# eSIM.net
KiCad netlist of a schematic drawn in Altium Designer
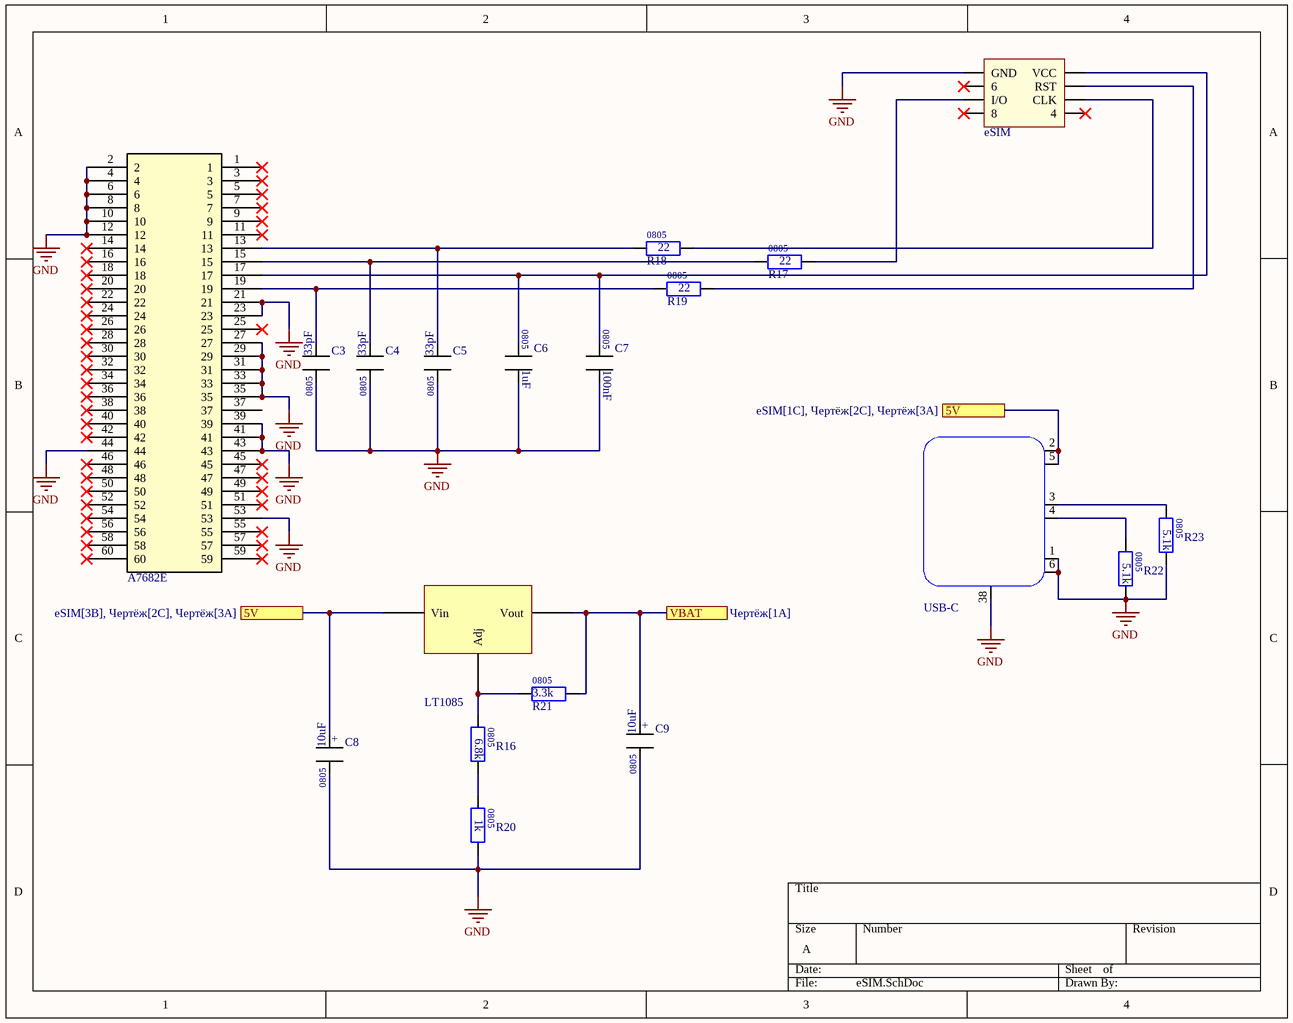
[diagram p0: eSIM.SchDoc]

(export (version "E")
  (design (tool "Eeschema 10.0.6"))
  (components
    (comp (ref "A7682E_J204") (value "A7682E") (footprint "A7682") (libsource (lib "Plat") (part "A7682E")))
    (comp (ref "C3")
      (value "CC080533pF")
      (footprint "СС0805")
      (description "CC0805_33pF")
      (libsource (lib "Component") (part "CC080533pF"))
    )
    (comp (ref "C4")
      (value "CC080533pF")
      (footprint "СС0805")
      (description "CC0805_33pF")
      (libsource (lib "Component") (part "CC080533pF"))
    )
    (comp (ref "C5")
      (value "CC080533pF")
      (footprint "СС0805")
      (description "CC0805_33pF")
      (libsource (lib "Component") (part "CC080533pF"))
    )
    (comp (ref "C6")
      (value "capacitor")
      (footprint "СС0805")
      (description "CC0805_1uF")
      (libsource (lib "Component") (part "CC08051uF"))
    )
    (comp (ref "C7")
      (value "capacitor")
      (footprint "СС0805")
      (description "CC0805_100nF")
      (libsource (lib "Component") (part "CC0805100nF"))
    )
    (comp (ref "C8")
      (value "capacitor")
      (footprint "CAP JAMOCON")
      (description "CE0805_10uF")
      (libsource (lib "Component") (part "CE080510uF"))
    )
    (comp (ref "C9")
      (value "capacitor")
      (footprint "CAP JAMOCON")
      (description "CE0805_10uF")
      (libsource (lib "Component") (part "CE080510uF"))
    )
    (comp (ref "eSIM1") (value "eSIM") (footprint "eSIM") (libsource (lib "Plat") (part "eSIM")))
    (comp (ref "LT1") (value "LT1085") (footprint "LD1058-1") (libsource (lib "Plat") (part "LT1085")))
    (comp (ref "R16")
      (value "Resistor")
      (footprint "R0805")
      (description "CR0805_6.8kR")
      (libsource (lib "Component") (part "CR08056.8kR"))
    )
    (comp (ref "R17")
      (value "Resistor")
      (footprint "R0805")
      (description "CR0805_22R")
      (libsource (lib "Component") (part "CR080522R"))
    )
    (comp (ref "R18")
      (value "Resistor")
      (footprint "R0805")
      (description "CR0805_22R")
      (libsource (lib "Component") (part "CR080522R"))
    )
    (comp (ref "R19")
      (value "Resistor")
      (footprint "R0805")
      (description "CR0805_22R")
      (libsource (lib "Component") (part "CR080522R"))
    )
    (comp (ref "R20")
      (value "Resistor")
      (footprint "R0805")
      (description "CR0805_1kR")
      (libsource (lib "Component") (part "CR08051kR"))
    )
    (comp (ref "R21")
      (value "Resistor")
      (footprint "R0805")
      (description "CR0805_3.3kR")
      (libsource (lib "Component") (part "CR08053.3kR"))
    )
    (comp (ref "R22")
      (value "Resistor")
      (footprint "R0805")
      (description "CR08055.1kR")
      (libsource (lib "Component") (part "CR08055.1kR"))
    )
    (comp (ref "R23")
      (value "Resistor")
      (footprint "R0805")
      (description "CR08055.1kR")
      (libsource (lib "Component") (part "CR08055.1kR"))
    )
    (comp (ref "USB-C1") (value "USB-C") (footprint "USB C") (libsource (lib "Plat") (part "USB-C")))
  )
  (nets
    (net (code "1") (name "/5V") (class "Default")
      (node (ref "C8") (pin "2") (pinfunction "2_2") (pintype "passive"))
      (node (ref "LT1") (pin "Vin") (pinfunction "Vin_Vin") (pintype "passive"))
      (node (ref "USB-C1") (pin "2") (pinfunction "VBAS_2") (pintype "passive"))
      (node (ref "USB-C1") (pin "5") (pinfunction "VBAS_5") (pintype "passive"))
    )
    (net (code "2") (name "/VBAT") (class "Default")
      (node (ref "C9") (pin "2") (pinfunction "2_2") (pintype "passive"))
      (node (ref "LT1") (pin "Vout") (pinfunction "Vout_Vout") (pintype "passive"))
      (node (ref "R21") (pin "1") (pinfunction "1_1") (pintype "passive"))
    )
    (net (code "3") (name "GND") (class "Default")
      (node (ref "A7682E_J204") (pin "10") (pinfunction "10_10") (pintype "passive"))
      (node (ref "A7682E_J204") (pin "12") (pinfunction "12_12") (pintype "passive"))
      (node (ref "A7682E_J204") (pin "2") (pinfunction "2_2") (pintype "passive"))
      (node (ref "A7682E_J204") (pin "21") (pinfunction "21_21") (pintype "passive"))
      (node (ref "A7682E_J204") (pin "23") (pinfunction "23_23") (pintype "passive"))
      (node (ref "A7682E_J204") (pin "27") (pinfunction "27_27") (pintype "passive"))
      (node (ref "A7682E_J204") (pin "29") (pinfunction "29_29") (pintype "passive"))
      (node (ref "A7682E_J204") (pin "31") (pinfunction "31_31") (pintype "passive"))
      (node (ref "A7682E_J204") (pin "33") (pinfunction "33_33") (pintype "passive"))
      (node (ref "A7682E_J204") (pin "35") (pinfunction "35_35") (pintype "passive"))
      (node (ref "A7682E_J204") (pin "39") (pinfunction "39_39") (pintype "passive"))
      (node (ref "A7682E_J204") (pin "4") (pinfunction "4_4") (pintype "passive"))
      (node (ref "A7682E_J204") (pin "41") (pinfunction "41_41") (pintype "passive"))
      (node (ref "A7682E_J204") (pin "43") (pinfunction "43_43") (pintype "passive"))
      (node (ref "A7682E_J204") (pin "44") (pinfunction "44_44") (pintype "passive"))
      (node (ref "A7682E_J204") (pin "53") (pinfunction "53_53") (pintype "passive"))
      (node (ref "A7682E_J204") (pin "6") (pinfunction "6_6") (pintype "passive"))
      (node (ref "A7682E_J204") (pin "8") (pinfunction "8_8") (pintype "passive"))
      (node (ref "C3") (pin "2") (pinfunction "2_2") (pintype "passive"))
      (node (ref "C4") (pin "2") (pinfunction "2_2") (pintype "passive"))
      (node (ref "C5") (pin "2") (pinfunction "2_2") (pintype "passive"))
      (node (ref "C6") (pin "2") (pinfunction "2_2") (pintype "passive"))
      (node (ref "C7") (pin "3") (pinfunction "3_3") (pintype "passive"))
      (node (ref "C8") (pin "3") (pinfunction "3_3") (pintype "passive"))
      (node (ref "C9") (pin "3") (pinfunction "3_3") (pintype "passive"))
      (node (ref "R20") (pin "1") (pinfunction "1_1") (pintype "passive"))
      (node (ref "R22") (pin "1") (pinfunction "1_1") (pintype "passive"))
      (node (ref "R23") (pin "1") (pinfunction "1_1") (pintype "passive"))
      (node (ref "USB-C1") (pin "1") (pinfunction "GND_1") (pintype "passive"))
      (node (ref "USB-C1") (pin "38") (pinfunction "SHIELD_38") (pintype "passive"))
      (node (ref "USB-C1") (pin "6") (pinfunction "GND_6") (pintype "passive"))
      (node (ref "eSIM1") (pin "5") (pinfunction "GND_5") (pintype "passive"))
    )
    (net (code "4") (name "Net-(A7682E_J204-Pad13)") (class "Default")
      (node (ref "A7682E_J204") (pin "13") (pinfunction "13_13") (pintype "passive"))
      (node (ref "C5") (pin "3") (pinfunction "3_3") (pintype "passive"))
      (node (ref "R18") (pin "0") (pinfunction "0_0") (pintype "passive"))
    )
    (net (code "5") (name "Net-(A7682E_J204-Pad15)") (class "Default")
      (node (ref "A7682E_J204") (pin "15") (pinfunction "15_15") (pintype "passive"))
      (node (ref "C4") (pin "3") (pinfunction "3_3") (pintype "passive"))
      (node (ref "R17") (pin "0") (pinfunction "0_0") (pintype "passive"))
    )
    (net (code "6") (name "Net-(A7682E_J204-Pad19)") (class "Default")
      (node (ref "A7682E_J204") (pin "19") (pinfunction "19_19") (pintype "passive"))
      (node (ref "C3") (pin "3") (pinfunction "3_3") (pintype "passive"))
      (node (ref "R19") (pin "0") (pinfunction "0_0") (pintype "passive"))
    )
    (net (code "7") (name "Net-(LT1-PadAdj)") (class "Default")
      (node (ref "LT1") (pin "Adj") (pinfunction "Adj_Adj") (pintype "passive"))
      (node (ref "R16") (pin "0") (pinfunction "0_0") (pintype "passive"))
      (node (ref "R21") (pin "0") (pinfunction "0_0") (pintype "passive"))
    )
    (net (code "8") (name "Net-(R16-Pad1)") (class "Default")
      (node (ref "R16") (pin "1") (pinfunction "1_1") (pintype "passive"))
      (node (ref "R20") (pin "0") (pinfunction "0_0") (pintype "passive"))
    )
    (net (code "9") (name "Net-(USB-C1-CC1)") (class "Default")
      (node (ref "R23") (pin "0") (pinfunction "0_0") (pintype "passive"))
      (node (ref "USB-C1") (pin "3") (pinfunction "CC1_3") (pintype "passive"))
    )
    (net (code "10") (name "Net-(USB-C1-CC2)") (class "Default")
      (node (ref "R22") (pin "0") (pinfunction "0_0") (pintype "passive"))
      (node (ref "USB-C1") (pin "4") (pinfunction "CC2_4") (pintype "passive"))
    )
    (net (code "11") (name "Net-(eSIM1-CLK)") (class "Default")
      (node (ref "R18") (pin "1") (pinfunction "1_1") (pintype "passive"))
      (node (ref "eSIM1") (pin "3") (pinfunction "CLK_3") (pintype "passive"))
    )
    (net (code "12") (name "Net-(eSIM1-I{slash}O)") (class "Default")
      (node (ref "R17") (pin "1") (pinfunction "1_1") (pintype "passive"))
      (node (ref "eSIM1") (pin "7") (pinfunction "I/O_7") (pintype "passive"))
    )
    (net (code "13") (name "Net-(eSIM1-RST)") (class "Default")
      (node (ref "R19") (pin "1") (pinfunction "1_1") (pintype "passive"))
      (node (ref "eSIM1") (pin "2") (pinfunction "RST_2") (pintype "passive"))
    )
    (net (code "14") (name "Net-(eSIM1-VCC)") (class "Default")
      (node (ref "A7682E_J204") (pin "17") (pinfunction "17_17") (pintype "passive"))
      (node (ref "C6") (pin "3") (pinfunction "3_3") (pintype "passive"))
      (node (ref "C7") (pin "2") (pinfunction "2_2") (pintype "passive"))
      (node (ref "eSIM1") (pin "1") (pinfunction "VCC_1") (pintype "passive"))
    )
    (net (code "15") (name "unconnected-(A7682E_J204-Pad1)") (class "Default")
      (node (ref "A7682E_J204") (pin "1") (pinfunction "1_1") (pintype "passive+no_connect"))
    )
    (net (code "16") (name "unconnected-(A7682E_J204-Pad3)") (class "Default")
      (node (ref "A7682E_J204") (pin "3") (pinfunction "3_3") (pintype "passive+no_connect"))
    )
    (net (code "17") (name "unconnected-(A7682E_J204-Pad5)") (class "Default")
      (node (ref "A7682E_J204") (pin "5") (pinfunction "5_5") (pintype "passive+no_connect"))
    )
    (net (code "18") (name "unconnected-(A7682E_J204-Pad7)") (class "Default")
      (node (ref "A7682E_J204") (pin "7") (pinfunction "7_7") (pintype "passive+no_connect"))
    )
    (net (code "19") (name "unconnected-(A7682E_J204-Pad9)") (class "Default")
      (node (ref "A7682E_J204") (pin "9") (pinfunction "9_9") (pintype "passive+no_connect"))
    )
    (net (code "20") (name "unconnected-(A7682E_J204-Pad11)") (class "Default")
      (node (ref "A7682E_J204") (pin "11") (pinfunction "11_11") (pintype "passive+no_connect"))
    )
    (net (code "21") (name "unconnected-(A7682E_J204-Pad14)") (class "Default")
      (node (ref "A7682E_J204") (pin "14") (pinfunction "14_14") (pintype "passive+no_connect"))
    )
    (net (code "22") (name "unconnected-(A7682E_J204-Pad16)") (class "Default")
      (node (ref "A7682E_J204") (pin "16") (pinfunction "16_16") (pintype "passive+no_connect"))
    )
    (net (code "23") (name "unconnected-(A7682E_J204-Pad18)") (class "Default")
      (node (ref "A7682E_J204") (pin "18") (pinfunction "18_18") (pintype "passive+no_connect"))
    )
    (net (code "24") (name "unconnected-(A7682E_J204-Pad20)") (class "Default")
      (node (ref "A7682E_J204") (pin "20") (pinfunction "20_20") (pintype "passive+no_connect"))
    )
    (net (code "25") (name "unconnected-(A7682E_J204-Pad22)") (class "Default")
      (node (ref "A7682E_J204") (pin "22") (pinfunction "22_22") (pintype "passive+no_connect"))
    )
    (net (code "26") (name "unconnected-(A7682E_J204-Pad24)") (class "Default")
      (node (ref "A7682E_J204") (pin "24") (pinfunction "24_24") (pintype "passive+no_connect"))
    )
    (net (code "27") (name "unconnected-(A7682E_J204-Pad25)") (class "Default")
      (node (ref "A7682E_J204") (pin "25") (pinfunction "25_25") (pintype "passive+no_connect"))
    )
    (net (code "28") (name "unconnected-(A7682E_J204-Pad26)") (class "Default")
      (node (ref "A7682E_J204") (pin "26") (pinfunction "26_26") (pintype "passive+no_connect"))
    )
    (net (code "29") (name "unconnected-(A7682E_J204-Pad28)") (class "Default")
      (node (ref "A7682E_J204") (pin "28") (pinfunction "28_28") (pintype "passive+no_connect"))
    )
    (net (code "30") (name "unconnected-(A7682E_J204-Pad30)") (class "Default")
      (node (ref "A7682E_J204") (pin "30") (pinfunction "30_30") (pintype "passive+no_connect"))
    )
    (net (code "31") (name "unconnected-(A7682E_J204-Pad32)") (class "Default")
      (node (ref "A7682E_J204") (pin "32") (pinfunction "32_32") (pintype "passive+no_connect"))
    )
    (net (code "32") (name "unconnected-(A7682E_J204-Pad34)") (class "Default")
      (node (ref "A7682E_J204") (pin "34") (pinfunction "34_34") (pintype "passive+no_connect"))
    )
    (net (code "33") (name "unconnected-(A7682E_J204-Pad36)") (class "Default")
      (node (ref "A7682E_J204") (pin "36") (pinfunction "36_36") (pintype "passive+no_connect"))
    )
    (net (code "34") (name "unconnected-(A7682E_J204-Pad37)") (class "Default")
      (node (ref "A7682E_J204") (pin "37") (pinfunction "37_37") (pintype "passive"))
    )
    (net (code "35") (name "unconnected-(A7682E_J204-Pad38)") (class "Default")
      (node (ref "A7682E_J204") (pin "38") (pinfunction "38_38") (pintype "passive+no_connect"))
    )
    (net (code "36") (name "unconnected-(A7682E_J204-Pad40)") (class "Default")
      (node (ref "A7682E_J204") (pin "40") (pinfunction "40_40") (pintype "passive+no_connect"))
    )
    (net (code "37") (name "unconnected-(A7682E_J204-Pad42)") (class "Default")
      (node (ref "A7682E_J204") (pin "42") (pinfunction "42_42") (pintype "passive+no_connect"))
    )
    (net (code "38") (name "unconnected-(A7682E_J204-Pad45)") (class "Default")
      (node (ref "A7682E_J204") (pin "45") (pinfunction "45_45") (pintype "passive+no_connect"))
    )
    (net (code "39") (name "unconnected-(A7682E_J204-Pad46)") (class "Default")
      (node (ref "A7682E_J204") (pin "46") (pinfunction "46_46") (pintype "passive+no_connect"))
    )
    (net (code "40") (name "unconnected-(A7682E_J204-Pad47)") (class "Default")
      (node (ref "A7682E_J204") (pin "47") (pinfunction "47_47") (pintype "passive+no_connect"))
    )
    (net (code "41") (name "unconnected-(A7682E_J204-Pad48)") (class "Default")
      (node (ref "A7682E_J204") (pin "48") (pinfunction "48_48") (pintype "passive+no_connect"))
    )
    (net (code "42") (name "unconnected-(A7682E_J204-Pad49)") (class "Default")
      (node (ref "A7682E_J204") (pin "49") (pinfunction "49_49") (pintype "passive+no_connect"))
    )
    (net (code "43") (name "unconnected-(A7682E_J204-Pad50)") (class "Default")
      (node (ref "A7682E_J204") (pin "50") (pinfunction "50_50") (pintype "passive+no_connect"))
    )
    (net (code "44") (name "unconnected-(A7682E_J204-Pad51)") (class "Default")
      (node (ref "A7682E_J204") (pin "51") (pinfunction "51_51") (pintype "passive+no_connect"))
    )
    (net (code "45") (name "unconnected-(A7682E_J204-Pad52)") (class "Default")
      (node (ref "A7682E_J204") (pin "52") (pinfunction "52_52") (pintype "passive+no_connect"))
    )
    (net (code "46") (name "unconnected-(A7682E_J204-Pad54)") (class "Default")
      (node (ref "A7682E_J204") (pin "54") (pinfunction "54_54") (pintype "passive+no_connect"))
    )
    (net (code "47") (name "unconnected-(A7682E_J204-Pad55)") (class "Default")
      (node (ref "A7682E_J204") (pin "55") (pinfunction "55_55") (pintype "passive+no_connect"))
    )
    (net (code "48") (name "unconnected-(A7682E_J204-Pad56)") (class "Default")
      (node (ref "A7682E_J204") (pin "56") (pinfunction "56_56") (pintype "passive+no_connect"))
    )
    (net (code "49") (name "unconnected-(A7682E_J204-Pad57)") (class "Default")
      (node (ref "A7682E_J204") (pin "57") (pinfunction "57_57") (pintype "passive+no_connect"))
    )
    (net (code "50") (name "unconnected-(A7682E_J204-Pad58)") (class "Default")
      (node (ref "A7682E_J204") (pin "58") (pinfunction "58_58") (pintype "passive+no_connect"))
    )
    (net (code "51") (name "unconnected-(A7682E_J204-Pad59)") (class "Default")
      (node (ref "A7682E_J204") (pin "59") (pinfunction "59_59") (pintype "passive+no_connect"))
    )
    (net (code "52") (name "unconnected-(A7682E_J204-Pad60)") (class "Default")
      (node (ref "A7682E_J204") (pin "60") (pinfunction "60_60") (pintype "passive+no_connect"))
    )
    (net (code "53") (name "unconnected-(eSIM1-Pad4)") (class "Default")
      (node (ref "eSIM1") (pin "4") (pinfunction "4_4") (pintype "passive+no_connect"))
    )
    (net (code "54") (name "unconnected-(eSIM1-Pad6)") (class "Default")
      (node (ref "eSIM1") (pin "6") (pinfunction "6_6") (pintype "passive+no_connect"))
    )
    (net (code "55") (name "unconnected-(eSIM1-Pad8)") (class "Default")
      (node (ref "eSIM1") (pin "8") (pinfunction "8_8") (pintype "passive+no_connect"))
    )
  )
)
